# LED1.net
KiCad netlist of a schematic drawn in Altium Designer
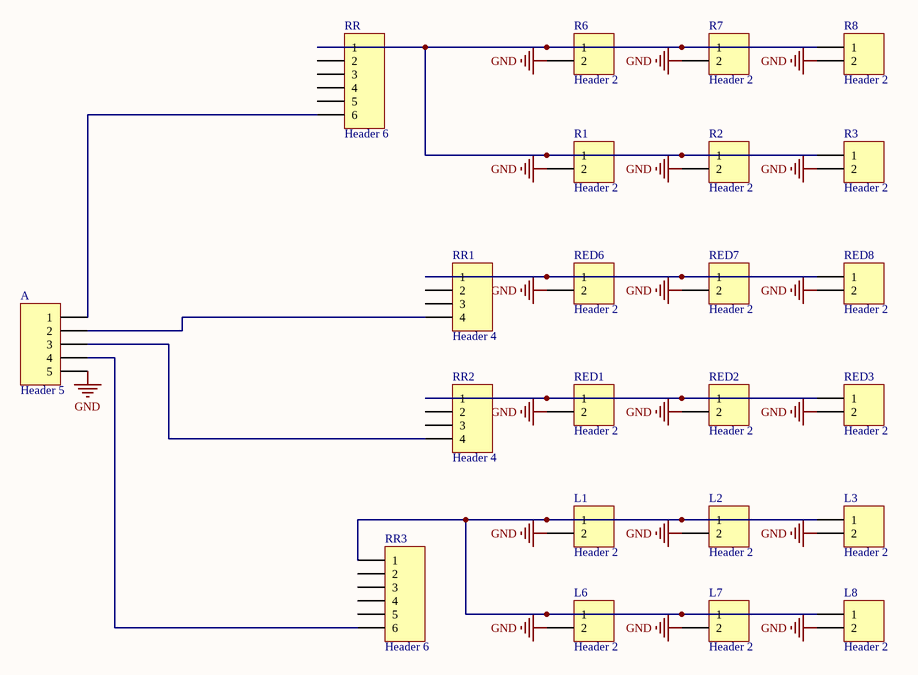
[diagram p0: LED1.SchDoc]

(export (version "E")
  (design (tool "Eeschema 10.0.6"))
  (components
    (comp (ref "A")
      (value "Header 5")
      (footprint "HDR1X5")
      (description "Header, 5-Pin")
      (fields (field (name "PUBLISHER") "Altium Limited"))
      (libsource (lib "Miscellaneous Connectors") (part "Header 5"))
    )
    (comp (ref "L1")
      (value "Header 2")
      (footprint "HDR1X2")
      (description "Header, 2-Pin")
      (fields (field (name "PUBLISHER") "Altium Limited"))
      (libsource (lib "Miscellaneous Connectors") (part "Header 2"))
    )
    (comp (ref "L2")
      (value "Header 2")
      (footprint "HDR1X2")
      (description "Header, 2-Pin")
      (fields (field (name "PUBLISHER") "Altium Limited"))
      (libsource (lib "Miscellaneous Connectors") (part "Header 2"))
    )
    (comp (ref "L3")
      (value "Header 2")
      (footprint "HDR1X2")
      (description "Header, 2-Pin")
      (fields (field (name "PUBLISHER") "Altium Limited"))
      (libsource (lib "Miscellaneous Connectors") (part "Header 2"))
    )
    (comp (ref "L6")
      (value "Header 2")
      (footprint "HDR1X2")
      (description "Header, 2-Pin")
      (fields (field (name "PUBLISHER") "Altium Limited"))
      (libsource (lib "Miscellaneous Connectors") (part "Header 2"))
    )
    (comp (ref "L7")
      (value "Header 2")
      (footprint "HDR1X2")
      (description "Header, 2-Pin")
      (fields (field (name "PUBLISHER") "Altium Limited"))
      (libsource (lib "Miscellaneous Connectors") (part "Header 2"))
    )
    (comp (ref "L8")
      (value "Header 2")
      (footprint "HDR1X2")
      (description "Header, 2-Pin")
      (fields (field (name "PUBLISHER") "Altium Limited"))
      (libsource (lib "Miscellaneous Connectors") (part "Header 2"))
    )
    (comp (ref "R1")
      (value "Header 2")
      (footprint "HDR1X2")
      (description "Header, 2-Pin")
      (fields (field (name "PUBLISHER") "Altium Limited"))
      (libsource (lib "Miscellaneous Connectors") (part "Header 2"))
    )
    (comp (ref "R2")
      (value "Header 2")
      (footprint "HDR1X2")
      (description "Header, 2-Pin")
      (fields (field (name "PUBLISHER") "Altium Limited"))
      (libsource (lib "Miscellaneous Connectors") (part "Header 2"))
    )
    (comp (ref "R3")
      (value "Header 2")
      (footprint "HDR1X2")
      (description "Header, 2-Pin")
      (fields (field (name "PUBLISHER") "Altium Limited"))
      (libsource (lib "Miscellaneous Connectors") (part "Header 2"))
    )
    (comp (ref "R6")
      (value "Header 2")
      (footprint "HDR1X2")
      (description "Header, 2-Pin")
      (fields (field (name "PUBLISHER") "Altium Limited"))
      (libsource (lib "Miscellaneous Connectors") (part "Header 2"))
    )
    (comp (ref "R7")
      (value "Header 2")
      (footprint "HDR1X2")
      (description "Header, 2-Pin")
      (fields (field (name "PUBLISHER") "Altium Limited"))
      (libsource (lib "Miscellaneous Connectors") (part "Header 2"))
    )
    (comp (ref "R8")
      (value "Header 2")
      (footprint "HDR1X2")
      (description "Header, 2-Pin")
      (fields (field (name "PUBLISHER") "Altium Limited"))
      (libsource (lib "Miscellaneous Connectors") (part "Header 2"))
    )
    (comp (ref "RED1")
      (value "Header 2")
      (footprint "HDR1X2")
      (description "Header, 2-Pin")
      (fields (field (name "PUBLISHER") "Altium Limited"))
      (libsource (lib "Miscellaneous Connectors") (part "Header 2"))
    )
    (comp (ref "RED2")
      (value "Header 2")
      (footprint "HDR1X2")
      (description "Header, 2-Pin")
      (fields (field (name "PUBLISHER") "Altium Limited"))
      (libsource (lib "Miscellaneous Connectors") (part "Header 2"))
    )
    (comp (ref "RED3")
      (value "Header 2")
      (footprint "HDR1X2")
      (description "Header, 2-Pin")
      (fields (field (name "PUBLISHER") "Altium Limited"))
      (libsource (lib "Miscellaneous Connectors") (part "Header 2"))
    )
    (comp (ref "RED6")
      (value "Header 2")
      (footprint "HDR1X2")
      (description "Header, 2-Pin")
      (fields (field (name "PUBLISHER") "Altium Limited"))
      (libsource (lib "Miscellaneous Connectors") (part "Header 2"))
    )
    (comp (ref "RED7")
      (value "Header 2")
      (footprint "HDR1X2")
      (description "Header, 2-Pin")
      (fields (field (name "PUBLISHER") "Altium Limited"))
      (libsource (lib "Miscellaneous Connectors") (part "Header 2"))
    )
    (comp (ref "RED8")
      (value "Header 2")
      (footprint "HDR1X2")
      (description "Header, 2-Pin")
      (fields (field (name "PUBLISHER") "Altium Limited"))
      (libsource (lib "Miscellaneous Connectors") (part "Header 2"))
    )
    (comp (ref "RR")
      (value "Header 6")
      (footprint "HDR1X6")
      (description "Header, 6-Pin")
      (fields (field (name "PUBLISHER") "Altium Limited"))
      (libsource (lib "Miscellaneous Connectors") (part "Header 6"))
    )
    (comp (ref "RR1")
      (value "Header 4")
      (footprint "HDR1X4")
      (description "Header, 4-Pin")
      (fields (field (name "PUBLISHER") "Altium Limited"))
      (libsource (lib "Miscellaneous Connectors") (part "Header 4"))
    )
    (comp (ref "RR2")
      (value "Header 4")
      (footprint "HDR1X4")
      (description "Header, 4-Pin")
      (fields (field (name "PUBLISHER") "Altium Limited"))
      (libsource (lib "Miscellaneous Connectors") (part "Header 4"))
    )
    (comp (ref "RR3")
      (value "Header 6")
      (footprint "HDR1X6")
      (description "Header, 6-Pin")
      (fields (field (name "PUBLISHER") "Altium Limited"))
      (libsource (lib "Miscellaneous Connectors") (part "Header 6"))
    )
  )
  (nets
    (net (code "1") (name "GND") (class "Default")
      (node (ref "A") (pin "5") (pinfunction "5_5") (pintype "passive"))
      (node (ref "L1") (pin "2") (pinfunction "2_2") (pintype "passive"))
      (node (ref "L2") (pin "2") (pinfunction "2_2") (pintype "passive"))
      (node (ref "L3") (pin "2") (pinfunction "2_2") (pintype "passive"))
      (node (ref "L6") (pin "2") (pinfunction "2_2") (pintype "passive"))
      (node (ref "L7") (pin "2") (pinfunction "2_2") (pintype "passive"))
      (node (ref "L8") (pin "2") (pinfunction "2_2") (pintype "passive"))
      (node (ref "R1") (pin "2") (pinfunction "2_2") (pintype "passive"))
      (node (ref "R2") (pin "2") (pinfunction "2_2") (pintype "passive"))
      (node (ref "R3") (pin "2") (pinfunction "2_2") (pintype "passive"))
      (node (ref "R6") (pin "2") (pinfunction "2_2") (pintype "passive"))
      (node (ref "R7") (pin "2") (pinfunction "2_2") (pintype "passive"))
      (node (ref "R8") (pin "2") (pinfunction "2_2") (pintype "passive"))
      (node (ref "RED1") (pin "2") (pinfunction "2_2") (pintype "passive"))
      (node (ref "RED2") (pin "2") (pinfunction "2_2") (pintype "passive"))
      (node (ref "RED3") (pin "2") (pinfunction "2_2") (pintype "passive"))
      (node (ref "RED6") (pin "2") (pinfunction "2_2") (pintype "passive"))
      (node (ref "RED7") (pin "2") (pinfunction "2_2") (pintype "passive"))
      (node (ref "RED8") (pin "2") (pinfunction "2_2") (pintype "passive"))
    )
    (net (code "2") (name "Net-(A-Pad1)") (class "Default")
      (node (ref "A") (pin "1") (pinfunction "1_1") (pintype "passive"))
      (node (ref "RR") (pin "6") (pinfunction "6_6") (pintype "passive"))
    )
    (net (code "3") (name "Net-(A-Pad2)") (class "Default")
      (node (ref "A") (pin "2") (pinfunction "2_2") (pintype "passive"))
      (node (ref "RR1") (pin "4") (pinfunction "4_4") (pintype "passive"))
    )
    (net (code "4") (name "Net-(A-Pad3)") (class "Default")
      (node (ref "A") (pin "3") (pinfunction "3_3") (pintype "passive"))
      (node (ref "RR2") (pin "4") (pinfunction "4_4") (pintype "passive"))
    )
    (net (code "5") (name "Net-(A-Pad4)") (class "Default")
      (node (ref "A") (pin "4") (pinfunction "4_4") (pintype "passive"))
      (node (ref "RR3") (pin "6") (pinfunction "6_6") (pintype "passive"))
    )
    (net (code "6") (name "Net-(L1-Pad1)") (class "Default")
      (node (ref "L1") (pin "1") (pinfunction "1_1") (pintype "passive"))
      (node (ref "L2") (pin "1") (pinfunction "1_1") (pintype "passive"))
      (node (ref "L3") (pin "1") (pinfunction "1_1") (pintype "passive"))
      (node (ref "L6") (pin "1") (pinfunction "1_1") (pintype "passive"))
      (node (ref "L7") (pin "1") (pinfunction "1_1") (pintype "passive"))
      (node (ref "L8") (pin "1") (pinfunction "1_1") (pintype "passive"))
      (node (ref "RR3") (pin "1") (pinfunction "1_1") (pintype "passive"))
    )
    (net (code "7") (name "Net-(R1-Pad1)") (class "Default")
      (node (ref "R1") (pin "1") (pinfunction "1_1") (pintype "passive"))
      (node (ref "R2") (pin "1") (pinfunction "1_1") (pintype "passive"))
      (node (ref "R3") (pin "1") (pinfunction "1_1") (pintype "passive"))
      (node (ref "R6") (pin "1") (pinfunction "1_1") (pintype "passive"))
      (node (ref "R7") (pin "1") (pinfunction "1_1") (pintype "passive"))
      (node (ref "R8") (pin "1") (pinfunction "1_1") (pintype "passive"))
      (node (ref "RR") (pin "1") (pinfunction "1_1") (pintype "passive"))
    )
    (net (code "8") (name "Net-(RED1-Pad1)") (class "Default")
      (node (ref "RED1") (pin "1") (pinfunction "1_1") (pintype "passive"))
      (node (ref "RED2") (pin "1") (pinfunction "1_1") (pintype "passive"))
      (node (ref "RED3") (pin "1") (pinfunction "1_1") (pintype "passive"))
      (node (ref "RR2") (pin "1") (pinfunction "1_1") (pintype "passive"))
    )
    (net (code "9") (name "Net-(RED6-Pad1)") (class "Default")
      (node (ref "RED6") (pin "1") (pinfunction "1_1") (pintype "passive"))
      (node (ref "RED7") (pin "1") (pinfunction "1_1") (pintype "passive"))
      (node (ref "RED8") (pin "1") (pinfunction "1_1") (pintype "passive"))
      (node (ref "RR1") (pin "1") (pinfunction "1_1") (pintype "passive"))
    )
    (net (code "10") (name "unconnected-(RR-Pad2)") (class "Default")
      (node (ref "RR") (pin "2") (pinfunction "2_2") (pintype "passive"))
    )
    (net (code "11") (name "unconnected-(RR-Pad3)") (class "Default")
      (node (ref "RR") (pin "3") (pinfunction "3_3") (pintype "passive"))
    )
    (net (code "12") (name "unconnected-(RR-Pad4)") (class "Default")
      (node (ref "RR") (pin "4") (pinfunction "4_4") (pintype "passive"))
    )
    (net (code "13") (name "unconnected-(RR-Pad5)") (class "Default")
      (node (ref "RR") (pin "5") (pinfunction "5_5") (pintype "passive"))
    )
    (net (code "14") (name "unconnected-(RR1-Pad2)") (class "Default")
      (node (ref "RR1") (pin "2") (pinfunction "2_2") (pintype "passive"))
    )
    (net (code "15") (name "unconnected-(RR1-Pad3)") (class "Default")
      (node (ref "RR1") (pin "3") (pinfunction "3_3") (pintype "passive"))
    )
    (net (code "16") (name "unconnected-(RR2-Pad2)") (class "Default")
      (node (ref "RR2") (pin "2") (pinfunction "2_2") (pintype "passive"))
    )
    (net (code "17") (name "unconnected-(RR2-Pad3)") (class "Default")
      (node (ref "RR2") (pin "3") (pinfunction "3_3") (pintype "passive"))
    )
    (net (code "18") (name "unconnected-(RR3-Pad2)") (class "Default")
      (node (ref "RR3") (pin "2") (pinfunction "2_2") (pintype "passive"))
    )
    (net (code "19") (name "unconnected-(RR3-Pad3)") (class "Default")
      (node (ref "RR3") (pin "3") (pinfunction "3_3") (pintype "passive"))
    )
    (net (code "20") (name "unconnected-(RR3-Pad4)") (class "Default")
      (node (ref "RR3") (pin "4") (pinfunction "4_4") (pintype "passive"))
    )
    (net (code "21") (name "unconnected-(RR3-Pad5)") (class "Default")
      (node (ref "RR3") (pin "5") (pinfunction "5_5") (pintype "passive"))
    )
  )
)
